# audio_sw_-_daughter.net
KiCad netlist of a schematic drawn in EAGLE
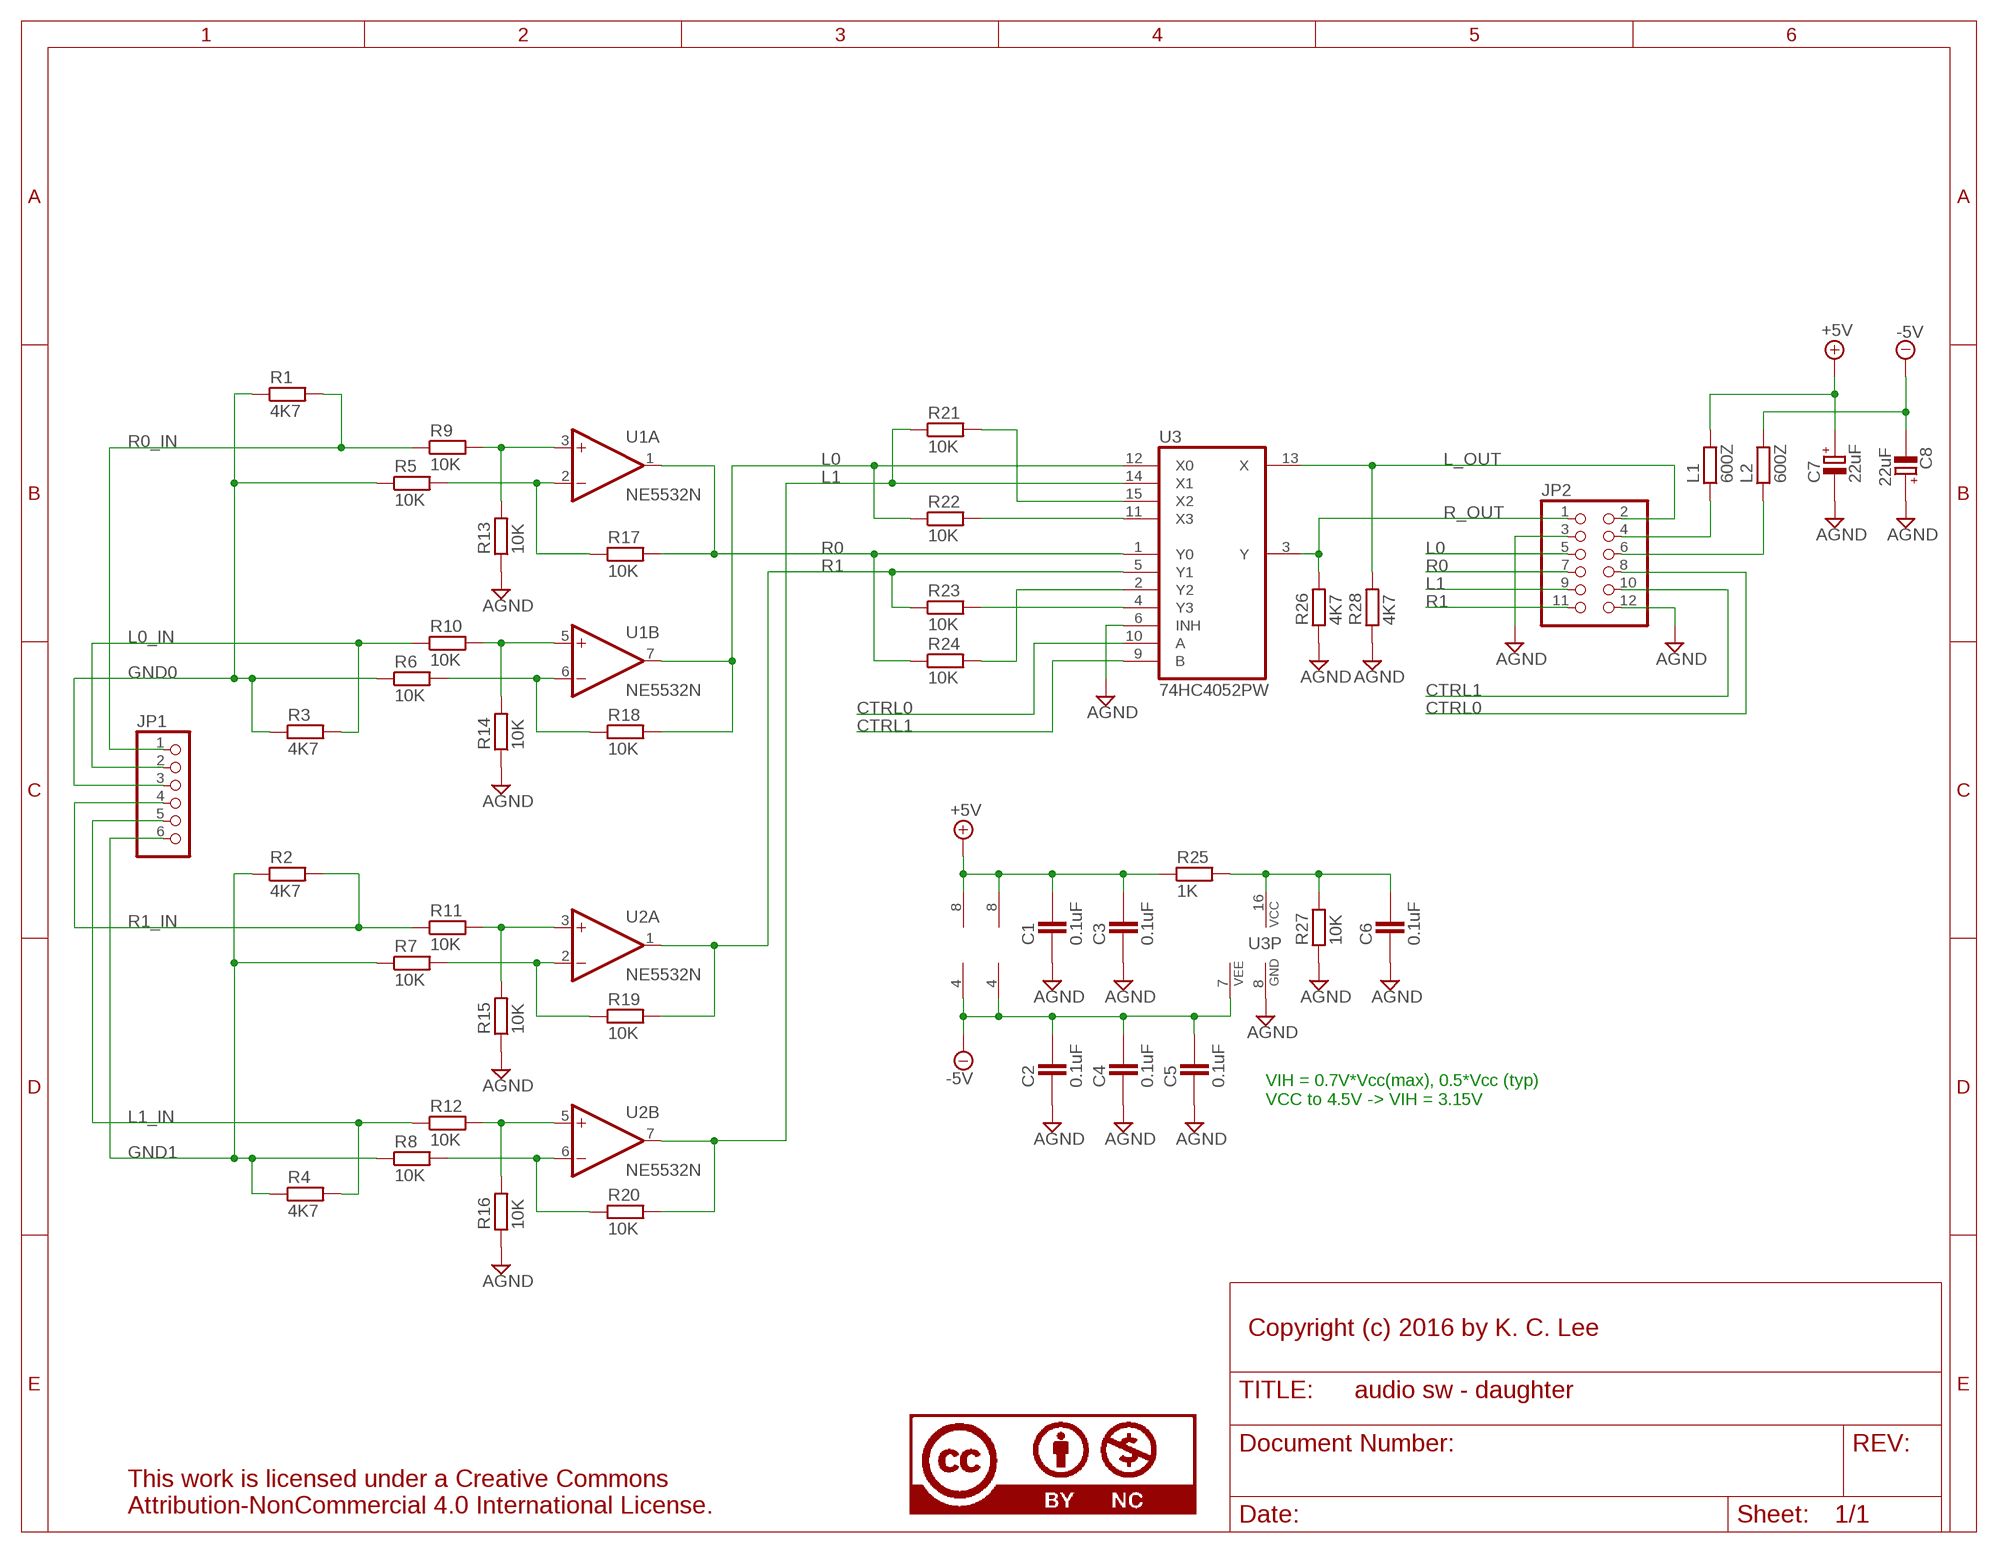
[diagram p0: schematic, sheet 1]

(export (version "E")
  (design (tool "Eeschema 10.0.6"))
  (components
    (comp (ref "C1")
      (value "0.1uF")
      (footprint "eagle-import:CAPC1608X92N")
      (libsource (lib "eagle-import") (part "CAPACITOR_0603"))
    )
    (comp (ref "C2")
      (value "0.1uF")
      (footprint "eagle-import:CAPC1608X92N")
      (libsource (lib "eagle-import") (part "CAPACITOR_0603"))
    )
    (comp (ref "C3")
      (value "0.1uF")
      (footprint "eagle-import:CAPC1608X92N")
      (libsource (lib "eagle-import") (part "CAPACITOR_0603"))
    )
    (comp (ref "C4")
      (value "0.1uF")
      (footprint "eagle-import:CAPC1608X92N")
      (libsource (lib "eagle-import") (part "CAPACITOR_0603"))
    )
    (comp (ref "C5")
      (value "0.1uF")
      (footprint "eagle-import:CAPC1608X92N")
      (libsource (lib "eagle-import") (part "CAPACITOR_0603"))
    )
    (comp (ref "C6")
      (value "0.1uF")
      (footprint "eagle-import:CAPC1608X92N")
      (libsource (lib "eagle-import") (part "CAPACITOR_0603"))
    )
    (comp (ref "C7")
      (value "22uF")
      (footprint "eagle-import:CAPMP6032X280N")
      (libsource (lib "eagle-import") (part "POLARISED_C_CASE"))
    )
    (comp (ref "C8")
      (value "22uF")
      (footprint "eagle-import:CAPMP6032X280N")
      (libsource (lib "eagle-import") (part "POLARISED_C_CASE"))
    )
    (comp (ref "JP1")
      (value "PINHD-1X6")
      (footprint "eagle-import:1X06")
      (libsource (lib "eagle-import") (part "PINHD-1X6"))
    )
    (comp (ref "JP2")
      (value "PINHD-2X6_2.54")
      (footprint "eagle-import:2X06")
      (libsource (lib "eagle-import") (part "PINHD-2X6_2.54"))
    )
    (comp (ref "L1")
      (value "600Z")
      (footprint "eagle-import:RESC2012X70N")
      (libsource (lib "eagle-import") (part "RESISTOR_0805"))
    )
    (comp (ref "L2")
      (value "600Z")
      (footprint "eagle-import:RESC2012X70N")
      (libsource (lib "eagle-import") (part "RESISTOR_0805"))
    )
    (comp (ref "LICENSE1")
      (value "CC-BY-NC100%")
      (footprint "eagle-import:CC-BY-NC-100")
      (libsource (lib "eagle-import") (part "CC-BY-NC100%"))
    )
    (comp (ref "R1")
      (value "4K7")
      (footprint "eagle-import:RESC1608X55N")
      (libsource (lib "eagle-import") (part "RESISTOR_0603"))
    )
    (comp (ref "R2")
      (value "4K7")
      (footprint "eagle-import:RESC1608X55N")
      (libsource (lib "eagle-import") (part "RESISTOR_0603"))
    )
    (comp (ref "R3")
      (value "4K7")
      (footprint "eagle-import:RESC1608X55N")
      (libsource (lib "eagle-import") (part "RESISTOR_0603"))
    )
    (comp (ref "R4")
      (value "4K7")
      (footprint "eagle-import:RESC1608X55N")
      (libsource (lib "eagle-import") (part "RESISTOR_0603"))
    )
    (comp (ref "R5")
      (value "10K")
      (footprint "eagle-import:RESC1608X55N")
      (libsource (lib "eagle-import") (part "RESISTOR_0603"))
    )
    (comp (ref "R6")
      (value "10K")
      (footprint "eagle-import:RESC1608X55N")
      (libsource (lib "eagle-import") (part "RESISTOR_0603"))
    )
    (comp (ref "R7")
      (value "10K")
      (footprint "eagle-import:RESC1608X55N")
      (libsource (lib "eagle-import") (part "RESISTOR_0603"))
    )
    (comp (ref "R8")
      (value "10K")
      (footprint "eagle-import:RESC1608X55N")
      (libsource (lib "eagle-import") (part "RESISTOR_0603"))
    )
    (comp (ref "R9")
      (value "10K")
      (footprint "eagle-import:RESC1608X55N")
      (libsource (lib "eagle-import") (part "RESISTOR_0603"))
    )
    (comp (ref "R10")
      (value "10K")
      (footprint "eagle-import:RESC1608X55N")
      (libsource (lib "eagle-import") (part "RESISTOR_0603"))
    )
    (comp (ref "R11")
      (value "10K")
      (footprint "eagle-import:RESC1608X55N")
      (libsource (lib "eagle-import") (part "RESISTOR_0603"))
    )
    (comp (ref "R12")
      (value "10K")
      (footprint "eagle-import:RESC1608X55N")
      (libsource (lib "eagle-import") (part "RESISTOR_0603"))
    )
    (comp (ref "R13")
      (value "10K")
      (footprint "eagle-import:RESC1608X55N")
      (libsource (lib "eagle-import") (part "RESISTOR_0603"))
    )
    (comp (ref "R14")
      (value "10K")
      (footprint "eagle-import:RESC1608X55N")
      (libsource (lib "eagle-import") (part "RESISTOR_0603"))
    )
    (comp (ref "R15")
      (value "10K")
      (footprint "eagle-import:RESC1608X55N")
      (libsource (lib "eagle-import") (part "RESISTOR_0603"))
    )
    (comp (ref "R16")
      (value "10K")
      (footprint "eagle-import:RESC1608X55N")
      (libsource (lib "eagle-import") (part "RESISTOR_0603"))
    )
    (comp (ref "R17")
      (value "10K")
      (footprint "eagle-import:RESC1608X55N")
      (libsource (lib "eagle-import") (part "RESISTOR_0603"))
    )
    (comp (ref "R18")
      (value "10K")
      (footprint "eagle-import:RESC1608X55N")
      (libsource (lib "eagle-import") (part "RESISTOR_0603"))
    )
    (comp (ref "R19")
      (value "10K")
      (footprint "eagle-import:RESC1608X55N")
      (libsource (lib "eagle-import") (part "RESISTOR_0603"))
    )
    (comp (ref "R20")
      (value "10K")
      (footprint "eagle-import:RESC1608X55N")
      (libsource (lib "eagle-import") (part "RESISTOR_0603"))
    )
    (comp (ref "R21")
      (value "10K")
      (footprint "eagle-import:RESC1608X55N")
      (libsource (lib "eagle-import") (part "RESISTOR_0603"))
    )
    (comp (ref "R22")
      (value "10K")
      (footprint "eagle-import:RESC1608X55N")
      (libsource (lib "eagle-import") (part "RESISTOR_0603"))
    )
    (comp (ref "R23")
      (value "10K")
      (footprint "eagle-import:RESC1608X55N")
      (libsource (lib "eagle-import") (part "RESISTOR_0603"))
    )
    (comp (ref "R24")
      (value "10K")
      (footprint "eagle-import:RESC1608X55N")
      (libsource (lib "eagle-import") (part "RESISTOR_0603"))
    )
    (comp (ref "R25")
      (value "1K")
      (footprint "eagle-import:RESC1608X55N")
      (libsource (lib "eagle-import") (part "RESISTOR_0603"))
    )
    (comp (ref "R26")
      (value "4K7")
      (footprint "eagle-import:RESC1608X55N")
      (libsource (lib "eagle-import") (part "RESISTOR_0603"))
    )
    (comp (ref "R27")
      (value "10K")
      (footprint "eagle-import:RESC1608X55N")
      (libsource (lib "eagle-import") (part "RESISTOR_0603"))
    )
    (comp (ref "R28")
      (value "4K7")
      (footprint "eagle-import:RESC1608X55N")
      (libsource (lib "eagle-import") (part "RESISTOR_0603"))
    )
    (comp (ref "U1")
      (value "NE5532N")
      (footprint "eagle-import:SO08")
      (libsource (lib "eagle-import") (part "LM358D"))
    )
    (comp (ref "U2")
      (value "NE5532N")
      (footprint "eagle-import:SO08")
      (libsource (lib "eagle-import") (part "LM358D"))
    )
    (comp (ref "U3")
      (value "74HC4052PW")
      (footprint "eagle-import:TSSOP16")
      (libsource (lib "eagle-import") (part "4052PW"))
    )
  )
  (nets
    (net (code "1") (name "+5V") (class "Default")
      (node (ref "C1") (pin "2") (pinfunction "2_2") (pintype "passive"))
      (node (ref "C3") (pin "2") (pinfunction "2_2") (pintype "passive"))
      (node (ref "C7") (pin "+") (pinfunction "+_+") (pintype "passive"))
      (node (ref "L1") (pin "2") (pinfunction "2_2") (pintype "passive"))
      (node (ref "R25") (pin "1") (pinfunction "1_1") (pintype "passive"))
      (node (ref "U1") (pin "8") (pinfunction "V+_8") (pintype "power_in"))
      (node (ref "U2") (pin "8") (pinfunction "V+_8") (pintype "power_in"))
    )
    (net (code "2") (name "-5V") (class "Default")
      (node (ref "C2") (pin "2") (pinfunction "2_2") (pintype "passive"))
      (node (ref "C4") (pin "2") (pinfunction "2_2") (pintype "passive"))
      (node (ref "C5") (pin "2") (pinfunction "2_2") (pintype "passive"))
      (node (ref "C8") (pin "-") (pinfunction "-_-") (pintype "passive"))
      (node (ref "L2") (pin "2") (pinfunction "2_2") (pintype "passive"))
      (node (ref "U1") (pin "4") (pinfunction "V-_4") (pintype "power_in"))
      (node (ref "U2") (pin "4") (pinfunction "V-_4") (pintype "power_in"))
      (node (ref "U3") (pin "7") (pinfunction "VEE_7") (pintype "power_in"))
    )
    (net (code "3") (name "/CTRL0") (class "Default")
      (node (ref "JP2") (pin "8") (pinfunction "8_8") (pintype "passive"))
      (node (ref "U3") (pin "10") (pinfunction "A_10") (pintype "input"))
    )
    (net (code "4") (name "/CTRL1") (class "Default")
      (node (ref "JP2") (pin "10") (pinfunction "10_10") (pintype "passive"))
      (node (ref "U3") (pin "9") (pinfunction "B_9") (pintype "input"))
    )
    (net (code "5") (name "/GND0") (class "Default")
      (node (ref "JP1") (pin "3") (pinfunction "3_3") (pintype "passive"))
      (node (ref "R1") (pin "1") (pinfunction "1_1") (pintype "passive"))
      (node (ref "R3") (pin "1") (pinfunction "1_1") (pintype "passive"))
      (node (ref "R5") (pin "1") (pinfunction "1_1") (pintype "passive"))
      (node (ref "R6") (pin "1") (pinfunction "1_1") (pintype "passive"))
    )
    (net (code "6") (name "/GND1") (class "Default")
      (node (ref "JP1") (pin "6") (pinfunction "6_6") (pintype "passive"))
      (node (ref "R2") (pin "1") (pinfunction "1_1") (pintype "passive"))
      (node (ref "R4") (pin "1") (pinfunction "1_1") (pintype "passive"))
      (node (ref "R7") (pin "1") (pinfunction "1_1") (pintype "passive"))
      (node (ref "R8") (pin "1") (pinfunction "1_1") (pintype "passive"))
    )
    (net (code "7") (name "/L0") (class "Default")
      (node (ref "JP2") (pin "5") (pinfunction "5_5") (pintype "passive"))
      (node (ref "R18") (pin "2") (pinfunction "2_2") (pintype "passive"))
      (node (ref "R22") (pin "1") (pinfunction "1_1") (pintype "passive"))
      (node (ref "U1") (pin "7") (pinfunction "OUT_7") (pintype "output"))
      (node (ref "U3") (pin "12") (pinfunction "X0_12") (pintype "bidirectional"))
    )
    (net (code "8") (name "/L0_IN") (class "Default")
      (node (ref "JP1") (pin "2") (pinfunction "2_2") (pintype "passive"))
      (node (ref "R10") (pin "1") (pinfunction "1_1") (pintype "passive"))
      (node (ref "R3") (pin "2") (pinfunction "2_2") (pintype "passive"))
    )
    (net (code "9") (name "/L1") (class "Default")
      (node (ref "JP2") (pin "9") (pinfunction "9_9") (pintype "passive"))
      (node (ref "R20") (pin "2") (pinfunction "2_2") (pintype "passive"))
      (node (ref "R21") (pin "1") (pinfunction "1_1") (pintype "passive"))
      (node (ref "U2") (pin "7") (pinfunction "OUT_7") (pintype "output"))
      (node (ref "U3") (pin "14") (pinfunction "X1_14") (pintype "bidirectional"))
    )
    (net (code "10") (name "/L1_IN") (class "Default")
      (node (ref "JP1") (pin "5") (pinfunction "5_5") (pintype "passive"))
      (node (ref "R12") (pin "1") (pinfunction "1_1") (pintype "passive"))
      (node (ref "R4") (pin "2") (pinfunction "2_2") (pintype "passive"))
    )
    (net (code "11") (name "/L_OUT") (class "Default")
      (node (ref "JP2") (pin "2") (pinfunction "2_2") (pintype "passive"))
      (node (ref "R28") (pin "2") (pinfunction "2_2") (pintype "passive"))
      (node (ref "U3") (pin "13") (pinfunction "X_13") (pintype "bidirectional"))
    )
    (net (code "12") (name "/R0") (class "Default")
      (node (ref "JP2") (pin "7") (pinfunction "7_7") (pintype "passive"))
      (node (ref "R17") (pin "2") (pinfunction "2_2") (pintype "passive"))
      (node (ref "R24") (pin "1") (pinfunction "1_1") (pintype "passive"))
      (node (ref "U1") (pin "1") (pinfunction "OUT_1") (pintype "output"))
      (node (ref "U3") (pin "1") (pinfunction "Y0_1") (pintype "bidirectional"))
    )
    (net (code "13") (name "/R0_IN") (class "Default")
      (node (ref "JP1") (pin "1") (pinfunction "1_1") (pintype "passive"))
      (node (ref "R1") (pin "2") (pinfunction "2_2") (pintype "passive"))
      (node (ref "R9") (pin "1") (pinfunction "1_1") (pintype "passive"))
    )
    (net (code "14") (name "/R1") (class "Default")
      (node (ref "JP2") (pin "11") (pinfunction "11_11") (pintype "passive"))
      (node (ref "R19") (pin "2") (pinfunction "2_2") (pintype "passive"))
      (node (ref "R23") (pin "1") (pinfunction "1_1") (pintype "passive"))
      (node (ref "U2") (pin "1") (pinfunction "OUT_1") (pintype "output"))
      (node (ref "U3") (pin "5") (pinfunction "Y1_5") (pintype "bidirectional"))
    )
    (net (code "15") (name "/R1_IN") (class "Default")
      (node (ref "JP1") (pin "4") (pinfunction "4_4") (pintype "passive"))
      (node (ref "R11") (pin "1") (pinfunction "1_1") (pintype "passive"))
      (node (ref "R2") (pin "2") (pinfunction "2_2") (pintype "passive"))
    )
    (net (code "16") (name "/R_OUT") (class "Default")
      (node (ref "JP2") (pin "1") (pinfunction "1_1") (pintype "passive"))
      (node (ref "R26") (pin "2") (pinfunction "2_2") (pintype "passive"))
      (node (ref "U3") (pin "3") (pinfunction "Y_3") (pintype "bidirectional"))
    )
    (net (code "17") (name "AGND") (class "Default")
      (node (ref "C1") (pin "1") (pinfunction "1_1") (pintype "passive"))
      (node (ref "C2") (pin "1") (pinfunction "1_1") (pintype "passive"))
      (node (ref "C3") (pin "1") (pinfunction "1_1") (pintype "passive"))
      (node (ref "C4") (pin "1") (pinfunction "1_1") (pintype "passive"))
      (node (ref "C5") (pin "1") (pinfunction "1_1") (pintype "passive"))
      (node (ref "C6") (pin "1") (pinfunction "1_1") (pintype "passive"))
      (node (ref "C7") (pin "-") (pinfunction "-_-") (pintype "passive"))
      (node (ref "C8") (pin "+") (pinfunction "+_+") (pintype "passive"))
      (node (ref "JP2") (pin "12") (pinfunction "12_12") (pintype "passive"))
      (node (ref "JP2") (pin "3") (pinfunction "3_3") (pintype "passive"))
      (node (ref "R13") (pin "1") (pinfunction "1_1") (pintype "passive"))
      (node (ref "R14") (pin "1") (pinfunction "1_1") (pintype "passive"))
      (node (ref "R15") (pin "1") (pinfunction "1_1") (pintype "passive"))
      (node (ref "R16") (pin "1") (pinfunction "1_1") (pintype "passive"))
      (node (ref "R26") (pin "1") (pinfunction "1_1") (pintype "passive"))
      (node (ref "R27") (pin "1") (pinfunction "1_1") (pintype "passive"))
      (node (ref "R28") (pin "1") (pinfunction "1_1") (pintype "passive"))
      (node (ref "U3") (pin "6") (pinfunction "INH_6") (pintype "input"))
      (node (ref "U3") (pin "8") (pinfunction "GND_8") (pintype "power_in"))
    )
    (net (code "18") (name "Net-(JP2-Pad4)") (class "Default")
      (node (ref "JP2") (pin "4") (pinfunction "4_4") (pintype "passive"))
      (node (ref "L1") (pin "1") (pinfunction "1_1") (pintype "passive"))
    )
    (net (code "19") (name "Net-(JP2-Pad6)") (class "Default")
      (node (ref "JP2") (pin "6") (pinfunction "6_6") (pintype "passive"))
      (node (ref "L2") (pin "1") (pinfunction "1_1") (pintype "passive"))
    )
    (net (code "20") (name "Net-(U1A-+IN)") (class "Default")
      (node (ref "R13") (pin "2") (pinfunction "2_2") (pintype "passive"))
      (node (ref "R9") (pin "2") (pinfunction "2_2") (pintype "passive"))
      (node (ref "U1") (pin "3") (pinfunction "+IN_3") (pintype "input"))
    )
    (net (code "21") (name "Net-(U1A--IN)") (class "Default")
      (node (ref "R17") (pin "1") (pinfunction "1_1") (pintype "passive"))
      (node (ref "R5") (pin "2") (pinfunction "2_2") (pintype "passive"))
      (node (ref "U1") (pin "2") (pinfunction "-IN_2") (pintype "input"))
    )
    (net (code "22") (name "Net-(U1B-+IN)") (class "Default")
      (node (ref "R10") (pin "2") (pinfunction "2_2") (pintype "passive"))
      (node (ref "R14") (pin "2") (pinfunction "2_2") (pintype "passive"))
      (node (ref "U1") (pin "5") (pinfunction "+IN_5") (pintype "input"))
    )
    (net (code "23") (name "Net-(U1B--IN)") (class "Default")
      (node (ref "R18") (pin "1") (pinfunction "1_1") (pintype "passive"))
      (node (ref "R6") (pin "2") (pinfunction "2_2") (pintype "passive"))
      (node (ref "U1") (pin "6") (pinfunction "-IN_6") (pintype "input"))
    )
    (net (code "24") (name "Net-(U2A-+IN)") (class "Default")
      (node (ref "R11") (pin "2") (pinfunction "2_2") (pintype "passive"))
      (node (ref "R15") (pin "2") (pinfunction "2_2") (pintype "passive"))
      (node (ref "U2") (pin "3") (pinfunction "+IN_3") (pintype "input"))
    )
    (net (code "25") (name "Net-(U2A--IN)") (class "Default")
      (node (ref "R19") (pin "1") (pinfunction "1_1") (pintype "passive"))
      (node (ref "R7") (pin "2") (pinfunction "2_2") (pintype "passive"))
      (node (ref "U2") (pin "2") (pinfunction "-IN_2") (pintype "input"))
    )
    (net (code "26") (name "Net-(U2B-+IN)") (class "Default")
      (node (ref "R12") (pin "2") (pinfunction "2_2") (pintype "passive"))
      (node (ref "R16") (pin "2") (pinfunction "2_2") (pintype "passive"))
      (node (ref "U2") (pin "5") (pinfunction "+IN_5") (pintype "input"))
    )
    (net (code "27") (name "Net-(U2B--IN)") (class "Default")
      (node (ref "R20") (pin "1") (pinfunction "1_1") (pintype "passive"))
      (node (ref "R8") (pin "2") (pinfunction "2_2") (pintype "passive"))
      (node (ref "U2") (pin "6") (pinfunction "-IN_6") (pintype "input"))
    )
    (net (code "28") (name "Net-(U3A-X2)") (class "Default")
      (node (ref "R21") (pin "2") (pinfunction "2_2") (pintype "passive"))
      (node (ref "U3") (pin "15") (pinfunction "X2_15") (pintype "bidirectional"))
    )
    (net (code "29") (name "Net-(U3A-X3)") (class "Default")
      (node (ref "R22") (pin "2") (pinfunction "2_2") (pintype "passive"))
      (node (ref "U3") (pin "11") (pinfunction "X3_11") (pintype "bidirectional"))
    )
    (net (code "30") (name "Net-(U3A-Y2)") (class "Default")
      (node (ref "R24") (pin "2") (pinfunction "2_2") (pintype "passive"))
      (node (ref "U3") (pin "2") (pinfunction "Y2_2") (pintype "bidirectional"))
    )
    (net (code "31") (name "Net-(U3A-Y3)") (class "Default")
      (node (ref "R23") (pin "2") (pinfunction "2_2") (pintype "passive"))
      (node (ref "U3") (pin "4") (pinfunction "Y3_4") (pintype "bidirectional"))
    )
    (net (code "32") (name "Net-(U3B-VCC)") (class "Default")
      (node (ref "C6") (pin "2") (pinfunction "2_2") (pintype "passive"))
      (node (ref "R25") (pin "2") (pinfunction "2_2") (pintype "passive"))
      (node (ref "R27") (pin "2") (pinfunction "2_2") (pintype "passive"))
      (node (ref "U3") (pin "16") (pinfunction "VCC_16") (pintype "power_in"))
    )
  )
)
